# PAGE111.net
KiCad netlist of a schematic drawn in Altium Designer
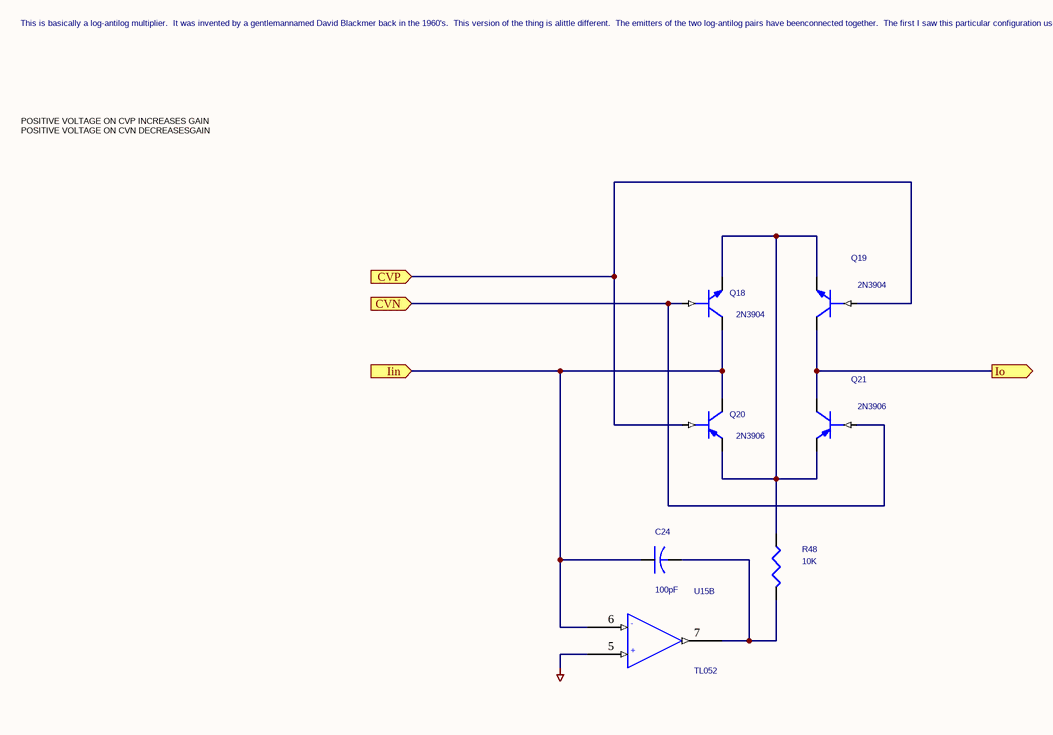
[diagram p0: PAGE111.SchDoc]

(export (version "E")
  (design (tool "Eeschema 10.0.6"))
  (components
    (comp (ref "C24") (value "100pF") (libsource (lib "*") (part "CAP_Dup1")))
    (comp (ref "Q18") (value "2N3904") (footprint "TO92") (libsource (lib "*") (part "NPN")))
    (comp (ref "Q19") (value "2N3904") (footprint "TO92") (libsource (lib "*") (part "NPN")))
    (comp (ref "Q20") (value "2N3906") (footprint "TO92") (libsource (lib "*") (part "PNP")))
    (comp (ref "Q21") (value "2N3906") (footprint "TO92") (libsource (lib "*") (part "PNP")))
    (comp (ref "R48") (value "10K") (libsource (lib "*") (part "R_Dup1")))
    (comp (ref "U15") (value "TL052") (footprint "DIP8") (libsource (lib "*") (part "GEN DUAL OPAMP-H")))
  )
  (nets
    (net (code "1") (name "/CVN") (class "Default")
      (node (ref "Q18") (pin "BASE") (pinfunction "BASE_BASE") (pintype "input"))
      (node (ref "Q21") (pin "BASE") (pinfunction "BASE_BASE") (pintype "input"))
    )
    (net (code "2") (name "/CVP") (class "Default")
      (node (ref "Q19") (pin "BASE") (pinfunction "BASE_BASE") (pintype "input"))
      (node (ref "Q20") (pin "BASE") (pinfunction "BASE_BASE") (pintype "input"))
    )
    (net (code "3") (name "/Iin") (class "Default")
      (node (ref "C24") (pin "1") (pinfunction "1_1") (pintype "passive"))
      (node (ref "Q18") (pin "COLLECTOR") (pinfunction "COLLECTOR_COLLECTOR") (pintype "passive"))
      (node (ref "Q20") (pin "COLLECTOR") (pinfunction "COLLECTOR_COLLECTOR") (pintype "passive"))
      (node (ref "U15") (pin "6") (pinfunction "-_6") (pintype "input"))
    )
    (net (code "4") (name "/Io") (class "Default")
      (node (ref "Q19") (pin "COLLECTOR") (pinfunction "COLLECTOR_COLLECTOR") (pintype "passive"))
      (node (ref "Q21") (pin "COLLECTOR") (pinfunction "COLLECTOR_COLLECTOR") (pintype "passive"))
    )
    (net (code "5") (name "AGND") (class "Default")
      (node (ref "U15") (pin "5") (pinfunction "+_5") (pintype "input"))
    )
    (net (code "6") (name "Net-(Q18-PadEMITTER)") (class "Default")
      (node (ref "Q18") (pin "EMITTER") (pinfunction "EMITTER_EMITTER") (pintype "passive"))
      (node (ref "Q19") (pin "EMITTER") (pinfunction "EMITTER_EMITTER") (pintype "passive"))
      (node (ref "Q20") (pin "EMITTER") (pinfunction "EMITTER_EMITTER") (pintype "passive"))
      (node (ref "Q21") (pin "EMITTER") (pinfunction "EMITTER_EMITTER") (pintype "passive"))
      (node (ref "R48") (pin "1") (pinfunction "1_1") (pintype "passive"))
    )
    (net (code "7") (name "Net-(U15B-OUT)") (class "Default")
      (node (ref "C24") (pin "2") (pinfunction "2_2") (pintype "passive"))
      (node (ref "R48") (pin "2") (pinfunction "2_2") (pintype "passive"))
      (node (ref "U15") (pin "7") (pinfunction "OUT_7") (pintype "output"))
    )
  )
)
